# CON_MC_XMC_J14_64PIN.net
KiCad netlist of a schematic drawn in Altium Designer
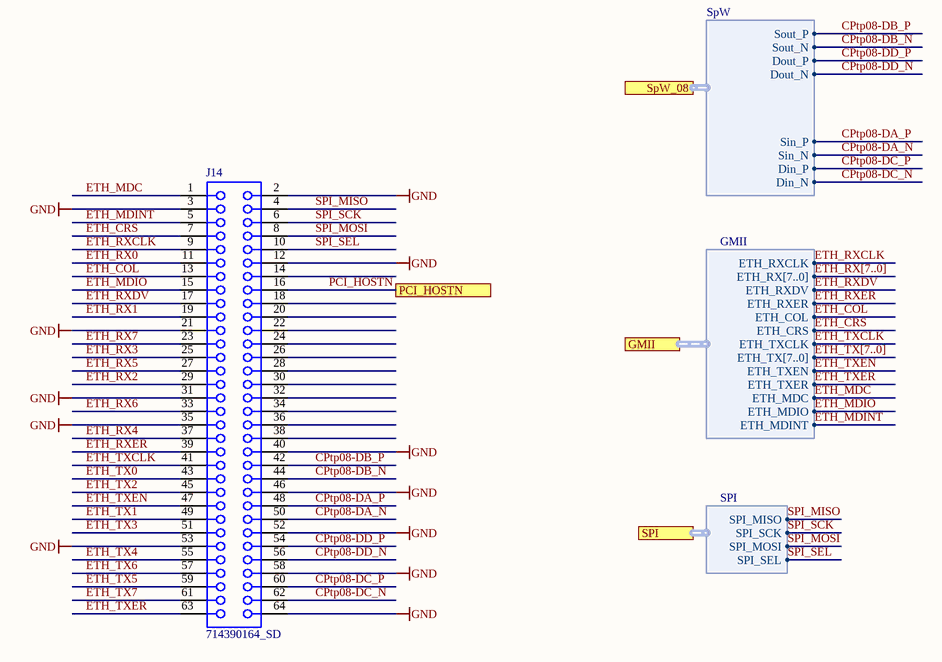
[diagram p0: CON_MC_XMC_J14_64PIN.SchDoc]

(export (version "E")
  (design (tool "Eeschema 10.0.6"))
  (components
    (comp (ref "J14")
      (value "714390164_SD")
      (footprint "BTB1-2V64F")
      (description "Board-to-Board Connector, Vertical, 2-Row, Pitch 1mm, 64-Position, Female")
      (fields (field (name "PUBLISHER") "Altium"))
      (libsource (lib "Altium Shanghai") (part "CMP-0001-00081-1"))
    )
  )
  (nets
    (net (code "4") (name "/CPtp08-DA_N") (class "Default")
      (node (ref "J14") (pin "50") (pinfunction "50_50") (pintype "passive"))
    )
    (net (code "5") (name "/CPtp08-DA_P") (class "Default")
      (node (ref "J14") (pin "48") (pinfunction "48_48") (pintype "passive"))
    )
    (net (code "6") (name "/CPtp08-DB_N") (class "Default")
      (node (ref "J14") (pin "44") (pinfunction "44_44") (pintype "passive"))
    )
    (net (code "7") (name "/CPtp08-DB_P") (class "Default")
      (node (ref "J14") (pin "42") (pinfunction "42_42") (pintype "passive"))
    )
    (net (code "8") (name "/CPtp08-DC_N") (class "Default")
      (node (ref "J14") (pin "62") (pinfunction "62_62") (pintype "passive"))
    )
    (net (code "9") (name "/CPtp08-DC_P") (class "Default")
      (node (ref "J14") (pin "60") (pinfunction "60_60") (pintype "passive"))
    )
    (net (code "10") (name "/CPtp08-DD_N") (class "Default")
      (node (ref "J14") (pin "56") (pinfunction "56_56") (pintype "passive"))
    )
    (net (code "11") (name "/CPtp08-DD_P") (class "Default")
      (node (ref "J14") (pin "54") (pinfunction "54_54") (pintype "passive"))
    )
    (net (code "12") (name "/ETH_COL") (class "Default")
      (node (ref "J14") (pin "13") (pinfunction "13_13") (pintype "passive"))
    )
    (net (code "13") (name "/ETH_CRS") (class "Default")
      (node (ref "J14") (pin "7") (pinfunction "7_7") (pintype "passive"))
    )
    (net (code "14") (name "/ETH_MDC") (class "Default")
      (node (ref "J14") (pin "1") (pinfunction "1_1") (pintype "passive"))
    )
    (net (code "15") (name "/ETH_MDINT") (class "Default")
      (node (ref "J14") (pin "5") (pinfunction "5_5") (pintype "passive"))
    )
    (net (code "16") (name "/ETH_MDIO") (class "Default")
      (node (ref "J14") (pin "15") (pinfunction "15_15") (pintype "passive"))
    )
    (net (code "17") (name "/ETH_RX0") (class "Default")
      (node (ref "J14") (pin "11") (pinfunction "11_11") (pintype "passive"))
    )
    (net (code "18") (name "/ETH_RX1") (class "Default")
      (node (ref "J14") (pin "19") (pinfunction "19_19") (pintype "passive"))
    )
    (net (code "19") (name "/ETH_RX2") (class "Default")
      (node (ref "J14") (pin "29") (pinfunction "29_29") (pintype "passive"))
    )
    (net (code "20") (name "/ETH_RX3") (class "Default")
      (node (ref "J14") (pin "25") (pinfunction "25_25") (pintype "passive"))
    )
    (net (code "21") (name "/ETH_RX4") (class "Default")
      (node (ref "J14") (pin "37") (pinfunction "37_37") (pintype "passive"))
    )
    (net (code "22") (name "/ETH_RX5") (class "Default")
      (node (ref "J14") (pin "27") (pinfunction "27_27") (pintype "passive"))
    )
    (net (code "23") (name "/ETH_RX6") (class "Default")
      (node (ref "J14") (pin "33") (pinfunction "33_33") (pintype "passive"))
    )
    (net (code "24") (name "/ETH_RX7") (class "Default")
      (node (ref "J14") (pin "23") (pinfunction "23_23") (pintype "passive"))
    )
    (net (code "25") (name "/ETH_RXCLK") (class "Default")
      (node (ref "J14") (pin "9") (pinfunction "9_9") (pintype "passive"))
    )
    (net (code "26") (name "/ETH_RXDV") (class "Default")
      (node (ref "J14") (pin "17") (pinfunction "17_17") (pintype "passive"))
    )
    (net (code "27") (name "/ETH_RXER") (class "Default")
      (node (ref "J14") (pin "39") (pinfunction "39_39") (pintype "passive"))
    )
    (net (code "29") (name "/ETH_TX0") (class "Default")
      (node (ref "J14") (pin "43") (pinfunction "43_43") (pintype "passive"))
    )
    (net (code "30") (name "/ETH_TX1") (class "Default")
      (node (ref "J14") (pin "49") (pinfunction "49_49") (pintype "passive"))
    )
    (net (code "31") (name "/ETH_TX2") (class "Default")
      (node (ref "J14") (pin "45") (pinfunction "45_45") (pintype "passive"))
    )
    (net (code "32") (name "/ETH_TX3") (class "Default")
      (node (ref "J14") (pin "51") (pinfunction "51_51") (pintype "passive"))
    )
    (net (code "33") (name "/ETH_TX4") (class "Default")
      (node (ref "J14") (pin "55") (pinfunction "55_55") (pintype "passive"))
    )
    (net (code "34") (name "/ETH_TX5") (class "Default")
      (node (ref "J14") (pin "59") (pinfunction "59_59") (pintype "passive"))
    )
    (net (code "35") (name "/ETH_TX6") (class "Default")
      (node (ref "J14") (pin "57") (pinfunction "57_57") (pintype "passive"))
    )
    (net (code "36") (name "/ETH_TX7") (class "Default")
      (node (ref "J14") (pin "61") (pinfunction "61_61") (pintype "passive"))
    )
    (net (code "37") (name "/ETH_TXCLK") (class "Default")
      (node (ref "J14") (pin "41") (pinfunction "41_41") (pintype "passive"))
    )
    (net (code "38") (name "/ETH_TXEN") (class "Default")
      (node (ref "J14") (pin "47") (pinfunction "47_47") (pintype "passive"))
    )
    (net (code "39") (name "/ETH_TXER") (class "Default")
      (node (ref "J14") (pin "63") (pinfunction "63_63") (pintype "passive"))
    )
    (net (code "41") (name "/PCI_HOSTN") (class "Default")
      (node (ref "J14") (pin "16") (pinfunction "16_16") (pintype "passive"))
    )
    (net (code "42") (name "/SPI_MISO") (class "Default")
      (node (ref "J14") (pin "4") (pinfunction "4_4") (pintype "passive"))
    )
    (net (code "43") (name "/SPI_MOSI") (class "Default")
      (node (ref "J14") (pin "8") (pinfunction "8_8") (pintype "passive"))
    )
    (net (code "44") (name "/SPI_SCK") (class "Default")
      (node (ref "J14") (pin "6") (pinfunction "6_6") (pintype "passive"))
    )
    (net (code "45") (name "/SPI_SEL") (class "Default")
      (node (ref "J14") (pin "10") (pinfunction "10_10") (pintype "passive"))
    )
    (net (code "49") (name "GND") (class "Default")
      (node (ref "J14") (pin "12") (pinfunction "12_12") (pintype "passive"))
      (node (ref "J14") (pin "2") (pinfunction "2_2") (pintype "passive"))
      (node (ref "J14") (pin "21") (pinfunction "21_21") (pintype "passive"))
      (node (ref "J14") (pin "3") (pinfunction "3_3") (pintype "passive"))
      (node (ref "J14") (pin "31") (pinfunction "31_31") (pintype "passive"))
      (node (ref "J14") (pin "35") (pinfunction "35_35") (pintype "passive"))
      (node (ref "J14") (pin "40") (pinfunction "40_40") (pintype "passive"))
      (node (ref "J14") (pin "46") (pinfunction "46_46") (pintype "passive"))
      (node (ref "J14") (pin "52") (pinfunction "52_52") (pintype "passive"))
      (node (ref "J14") (pin "53") (pinfunction "53_53") (pintype "passive"))
      (node (ref "J14") (pin "58") (pinfunction "58_58") (pintype "passive"))
      (node (ref "J14") (pin "64") (pinfunction "64_64") (pintype "passive"))
    )
    (net (code "50") (name "unconnected-(J14-Pad14)") (class "Default")
      (node (ref "J14") (pin "14") (pinfunction "14_14") (pintype "passive"))
    )
    (net (code "51") (name "unconnected-(J14-Pad18)") (class "Default")
      (node (ref "J14") (pin "18") (pinfunction "18_18") (pintype "passive"))
    )
    (net (code "52") (name "unconnected-(J14-Pad20)") (class "Default")
      (node (ref "J14") (pin "20") (pinfunction "20_20") (pintype "passive"))
    )
    (net (code "53") (name "unconnected-(J14-Pad22)") (class "Default")
      (node (ref "J14") (pin "22") (pinfunction "22_22") (pintype "passive"))
    )
    (net (code "54") (name "unconnected-(J14-Pad24)") (class "Default")
      (node (ref "J14") (pin "24") (pinfunction "24_24") (pintype "passive"))
    )
    (net (code "55") (name "unconnected-(J14-Pad26)") (class "Default")
      (node (ref "J14") (pin "26") (pinfunction "26_26") (pintype "passive"))
    )
    (net (code "56") (name "unconnected-(J14-Pad28)") (class "Default")
      (node (ref "J14") (pin "28") (pinfunction "28_28") (pintype "passive"))
    )
    (net (code "57") (name "unconnected-(J14-Pad30)") (class "Default")
      (node (ref "J14") (pin "30") (pinfunction "30_30") (pintype "passive"))
    )
    (net (code "58") (name "unconnected-(J14-Pad32)") (class "Default")
      (node (ref "J14") (pin "32") (pinfunction "32_32") (pintype "passive"))
    )
    (net (code "59") (name "unconnected-(J14-Pad34)") (class "Default")
      (node (ref "J14") (pin "34") (pinfunction "34_34") (pintype "passive"))
    )
    (net (code "60") (name "unconnected-(J14-Pad36)") (class "Default")
      (node (ref "J14") (pin "36") (pinfunction "36_36") (pintype "passive"))
    )
    (net (code "61") (name "unconnected-(J14-Pad38)") (class "Default")
      (node (ref "J14") (pin "38") (pinfunction "38_38") (pintype "passive"))
    )
  )
)
